# schematic.net
KiCad netlist of a schematic drawn in EasyEDA
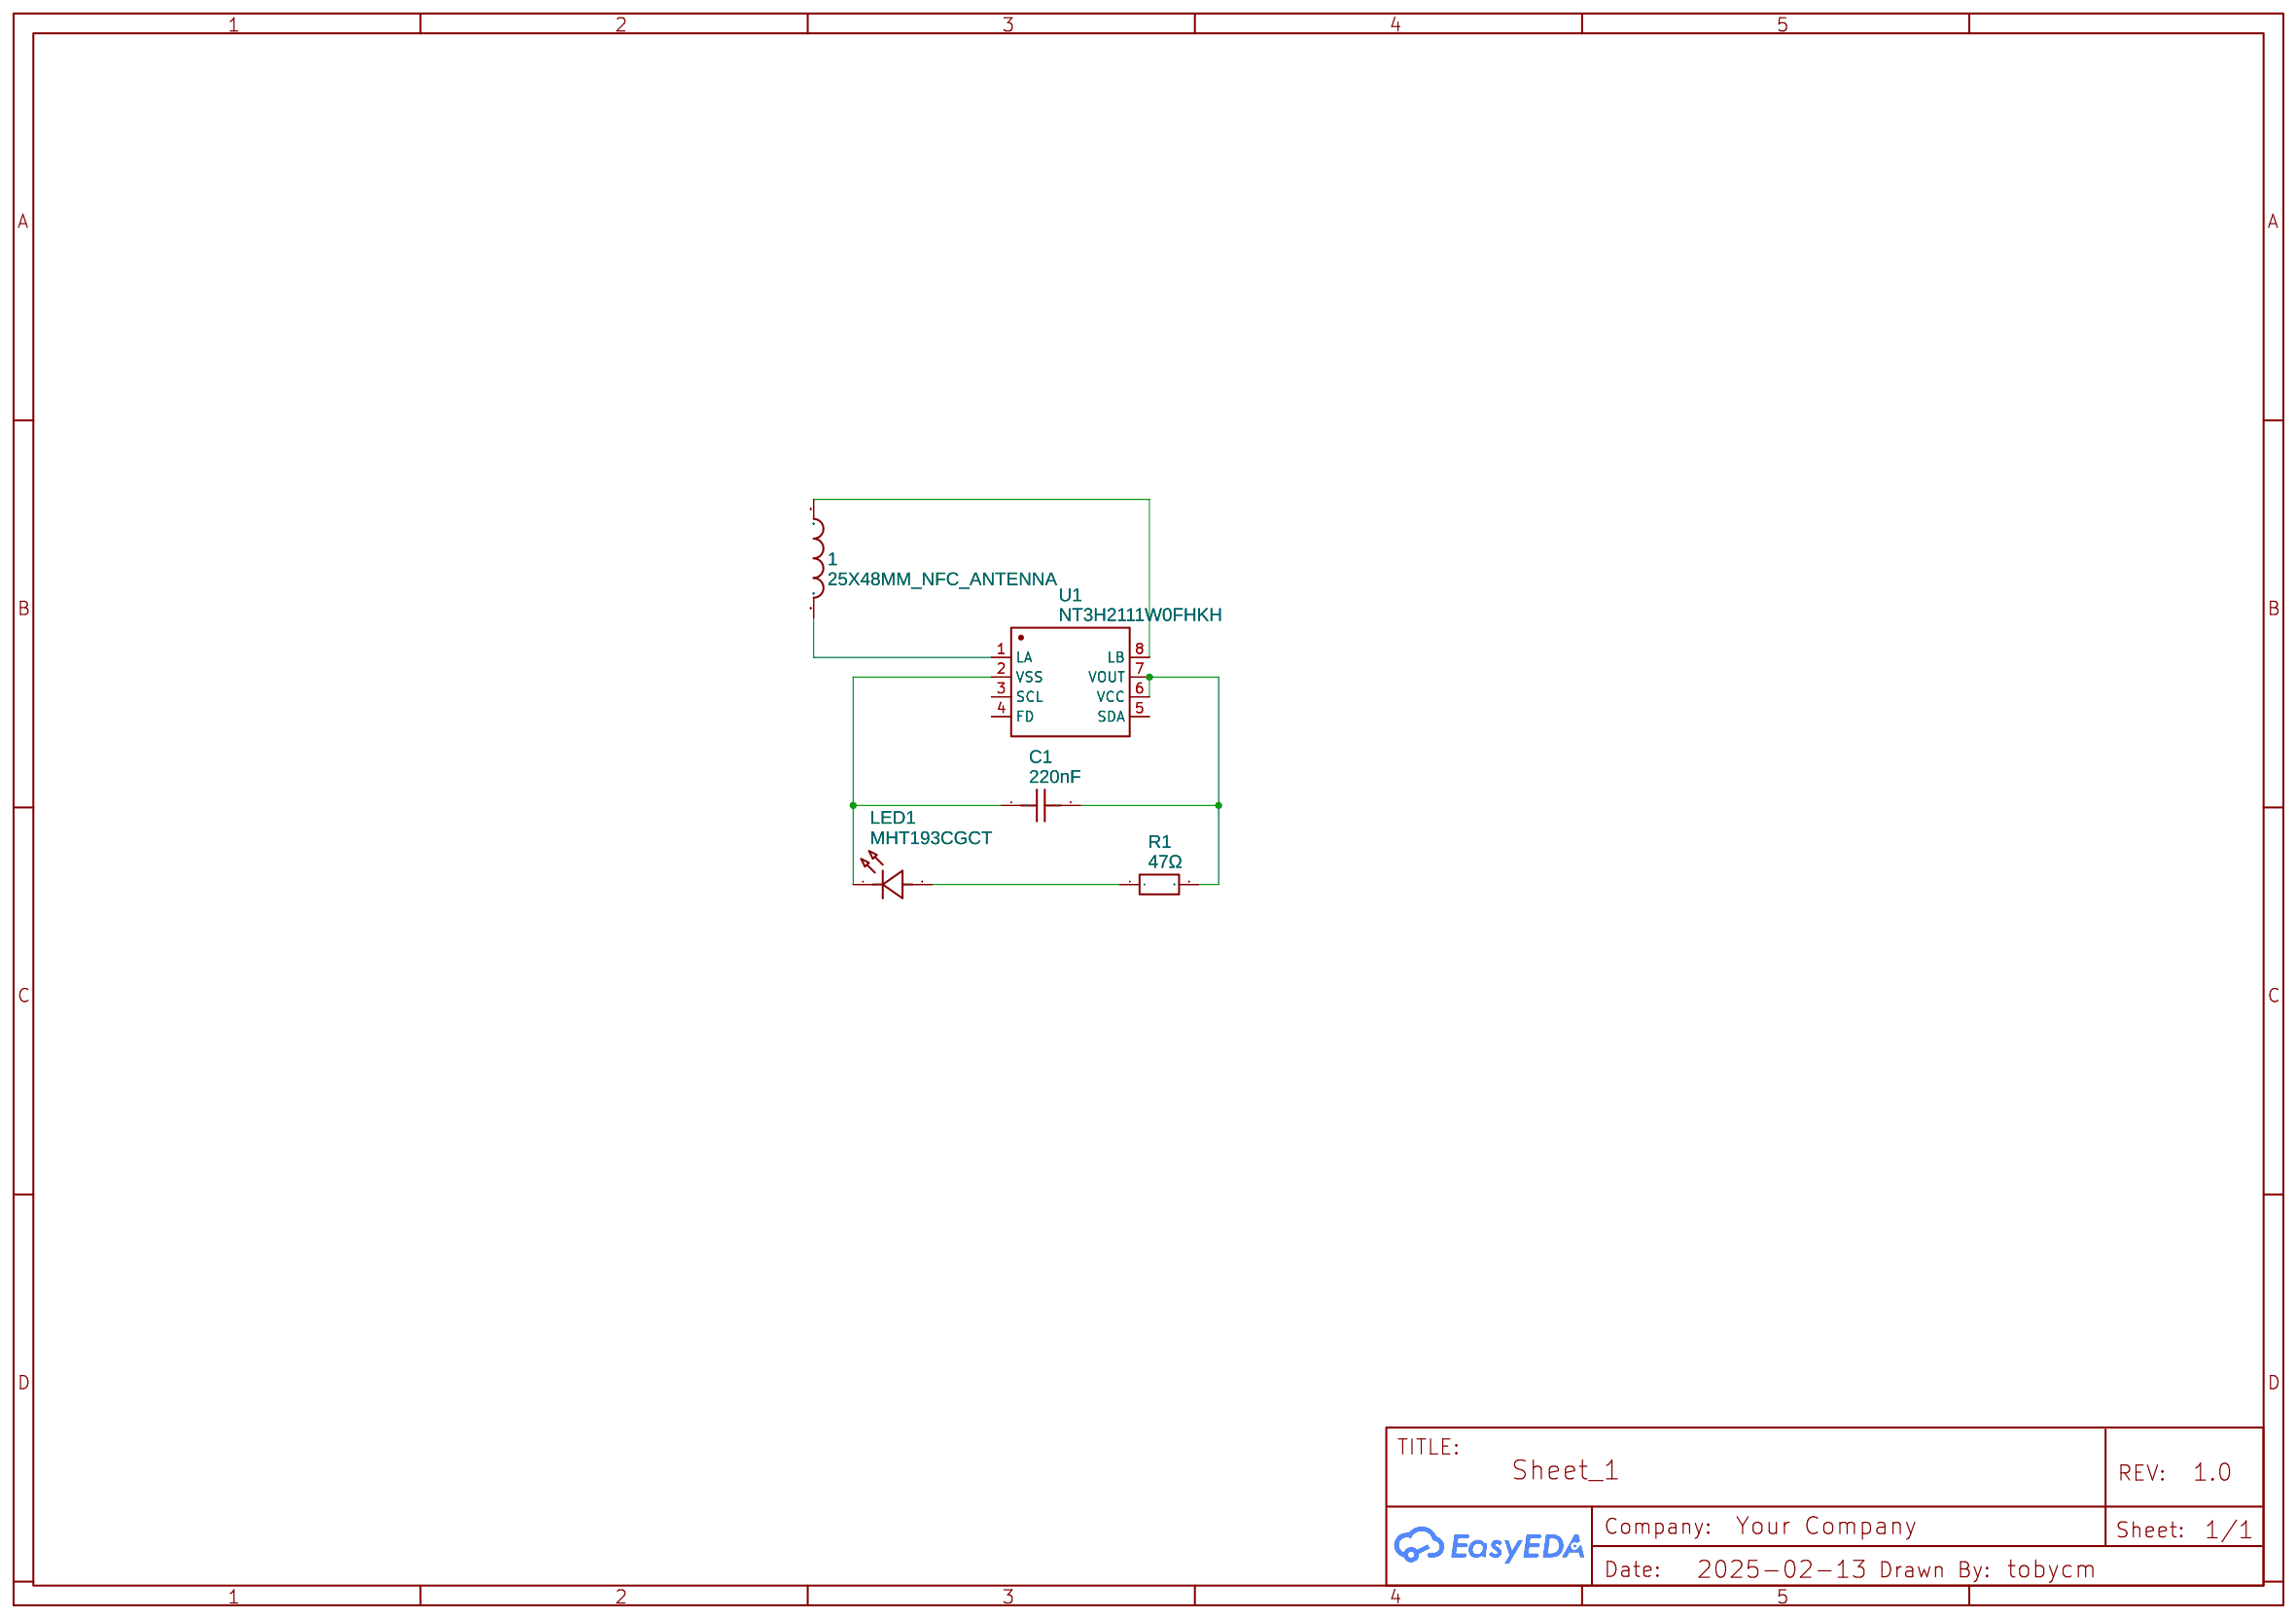
[diagram p0: schematic sheet]

(export (version "E")
  (design (tool "Eeschema 10.0.6"))
  (components
    (comp (ref "1") (value "25X48MM_NFC_ANTENNA") (libsource (lib "") (part "25X48MM_NFC_ANTENNA")))
    (comp (ref "C1")
      (value "220nF")
      (fields
        (field (name "Manufacturer Part") "CC0603KRX5R7BB224")
        (field (name "Manufacturer") "YAGEO(国巨)")
      )
      (libsource (lib "") (part "CC0603KRX5R7BB224"))
    )
    (comp (ref "LED1")
      (value "MHT193CGCT")
      (fields (field (name "Manufacturer") "MEIHUA(美华)"))
      (libsource (lib "") (part "MHT193CGCT"))
    )
    (comp (ref "R1")
      (value "47Ω")
      (fields (field (name "Manufacturer Part") "MO1/4W-47Ω±5%-ST52") (field (name "Manufacturer") "VO(翔胜)"))
      (libsource (lib "") (part "MO1/4W-47Ω±5%-ST52"))
    )
    (comp (ref "U1")
      (value "NT3H2111W0FHKH")
      (fields (field (name "Manufacturer") "NXP(恩智浦)"))
      (libsource (lib "") (part "NT3H2111W0FHKH"))
    )
  )
  (nets
    (net (code "1") (name "Net-(LED1-A)") (class "Default")
      (node (ref "LED1") (pin "2") (pinfunction "A_2") (pintype "unspecified"))
      (node (ref "R1") (pin "1") (pinfunction "1_1") (pintype "unspecified"))
    )
    (net (code "2") (name "Net-(LED1-K)") (class "Default")
      (node (ref "C1") (pin "1") (pinfunction "1_1") (pintype "unspecified"))
      (node (ref "LED1") (pin "1") (pinfunction "K_1") (pintype "unspecified"))
      (node (ref "U1") (pin "2") (pinfunction "VSS_2") (pintype "unspecified"))
    )
    (net (code "3") (name "Net-(U1-LA)") (class "Default")
      (node (ref "1") (pin "P$2") (pinfunction "P$2_P$2") (pintype "bidirectional"))
      (node (ref "U1") (pin "1") (pinfunction "LA_1") (pintype "unspecified"))
    )
    (net (code "4") (name "Net-(U1-LB)") (class "Default")
      (node (ref "1") (pin "P$1") (pinfunction "P$1_P$1") (pintype "bidirectional"))
      (node (ref "U1") (pin "8") (pinfunction "LB_8") (pintype "unspecified"))
    )
    (net (code "5") (name "Net-(U1-VCC)") (class "Default")
      (node (ref "C1") (pin "2") (pinfunction "2_2") (pintype "unspecified"))
      (node (ref "R1") (pin "2") (pinfunction "2_2") (pintype "unspecified"))
      (node (ref "U1") (pin "6") (pinfunction "VCC_6") (pintype "unspecified"))
      (node (ref "U1") (pin "7") (pinfunction "VOUT_7") (pintype "unspecified"))
    )
    (net (code "6") (name "unconnected-(U1-FD-Pad4)") (class "Default")
      (node (ref "U1") (pin "4") (pinfunction "FD_4") (pintype "unspecified"))
    )
    (net (code "7") (name "unconnected-(U1-SCL-Pad3)") (class "Default")
      (node (ref "U1") (pin "3") (pinfunction "SCL_3") (pintype "unspecified"))
    )
    (net (code "8") (name "unconnected-(U1-SDA-Pad5)") (class "Default")
      (node (ref "U1") (pin "5") (pinfunction "SDA_5") (pintype "unspecified"))
    )
  )
)
